# example_led.net
KiCad netlist of a schematic drawn in EAGLE
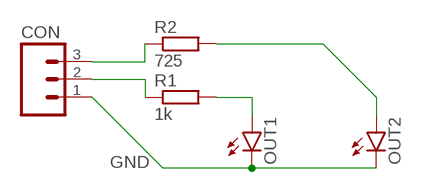
[diagram p0: schematic, sheet 1]

(export (version "E")
  (design (tool "Eeschema 10.0.6"))
  (components
    (comp (ref "CON")
      (value "M03")
      (footprint "eagle-import:03P")
      (libsource (lib "eagle-import") (part "M03"))
    )
    (comp (ref "OUT1")
      (value "LED5MM")
      (footprint "eagle-import:LED5MM")
      (libsource (lib "eagle-import") (part "LED5MM"))
    )
    (comp (ref "OUT2")
      (value "LED5MM")
      (footprint "eagle-import:LED5MM")
      (libsource (lib "eagle-import") (part "LED5MM"))
    )
    (comp (ref "R1")
      (value "1k")
      (footprint "eagle-import:0204_7")
      (libsource (lib "eagle-import") (part "R-EU_0204/7"))
    )
    (comp (ref "R2")
      (value "725")
      (footprint "eagle-import:0204_7")
      (libsource (lib "eagle-import") (part "R-EU_0204/7"))
    )
  )
  (nets
    (net (code "1") (name "GND") (class "Default")
      (node (ref "CON") (pin "1") (pinfunction "1_1") (pintype "passive"))
      (node (ref "OUT1") (pin "K") (pinfunction "C_K") (pintype "passive"))
      (node (ref "OUT2") (pin "K") (pinfunction "C_K") (pintype "passive"))
    )
    (net (code "2") (name "Net-(CON-Pad2)") (class "Default")
      (node (ref "CON") (pin "2") (pinfunction "2_2") (pintype "passive"))
      (node (ref "R1") (pin "1") (pinfunction "1_1") (pintype "passive"))
    )
    (net (code "3") (name "Net-(CON-Pad3)") (class "Default")
      (node (ref "CON") (pin "3") (pinfunction "3_3") (pintype "passive"))
      (node (ref "R2") (pin "1") (pinfunction "1_1") (pintype "passive"))
    )
    (net (code "4") (name "Net-(OUT1-PadA)") (class "Default")
      (node (ref "OUT1") (pin "A") (pinfunction "A_A") (pintype "passive"))
      (node (ref "R1") (pin "2") (pinfunction "2_2") (pintype "passive"))
    )
    (net (code "5") (name "Net-(OUT2-PadA)") (class "Default")
      (node (ref "OUT2") (pin "A") (pinfunction "A_A") (pintype "passive"))
      (node (ref "R2") (pin "2") (pinfunction "2_2") (pintype "passive"))
    )
  )
)
